# rcl_mini_v0_1.net
KiCad netlist of a schematic drawn in EAGLE
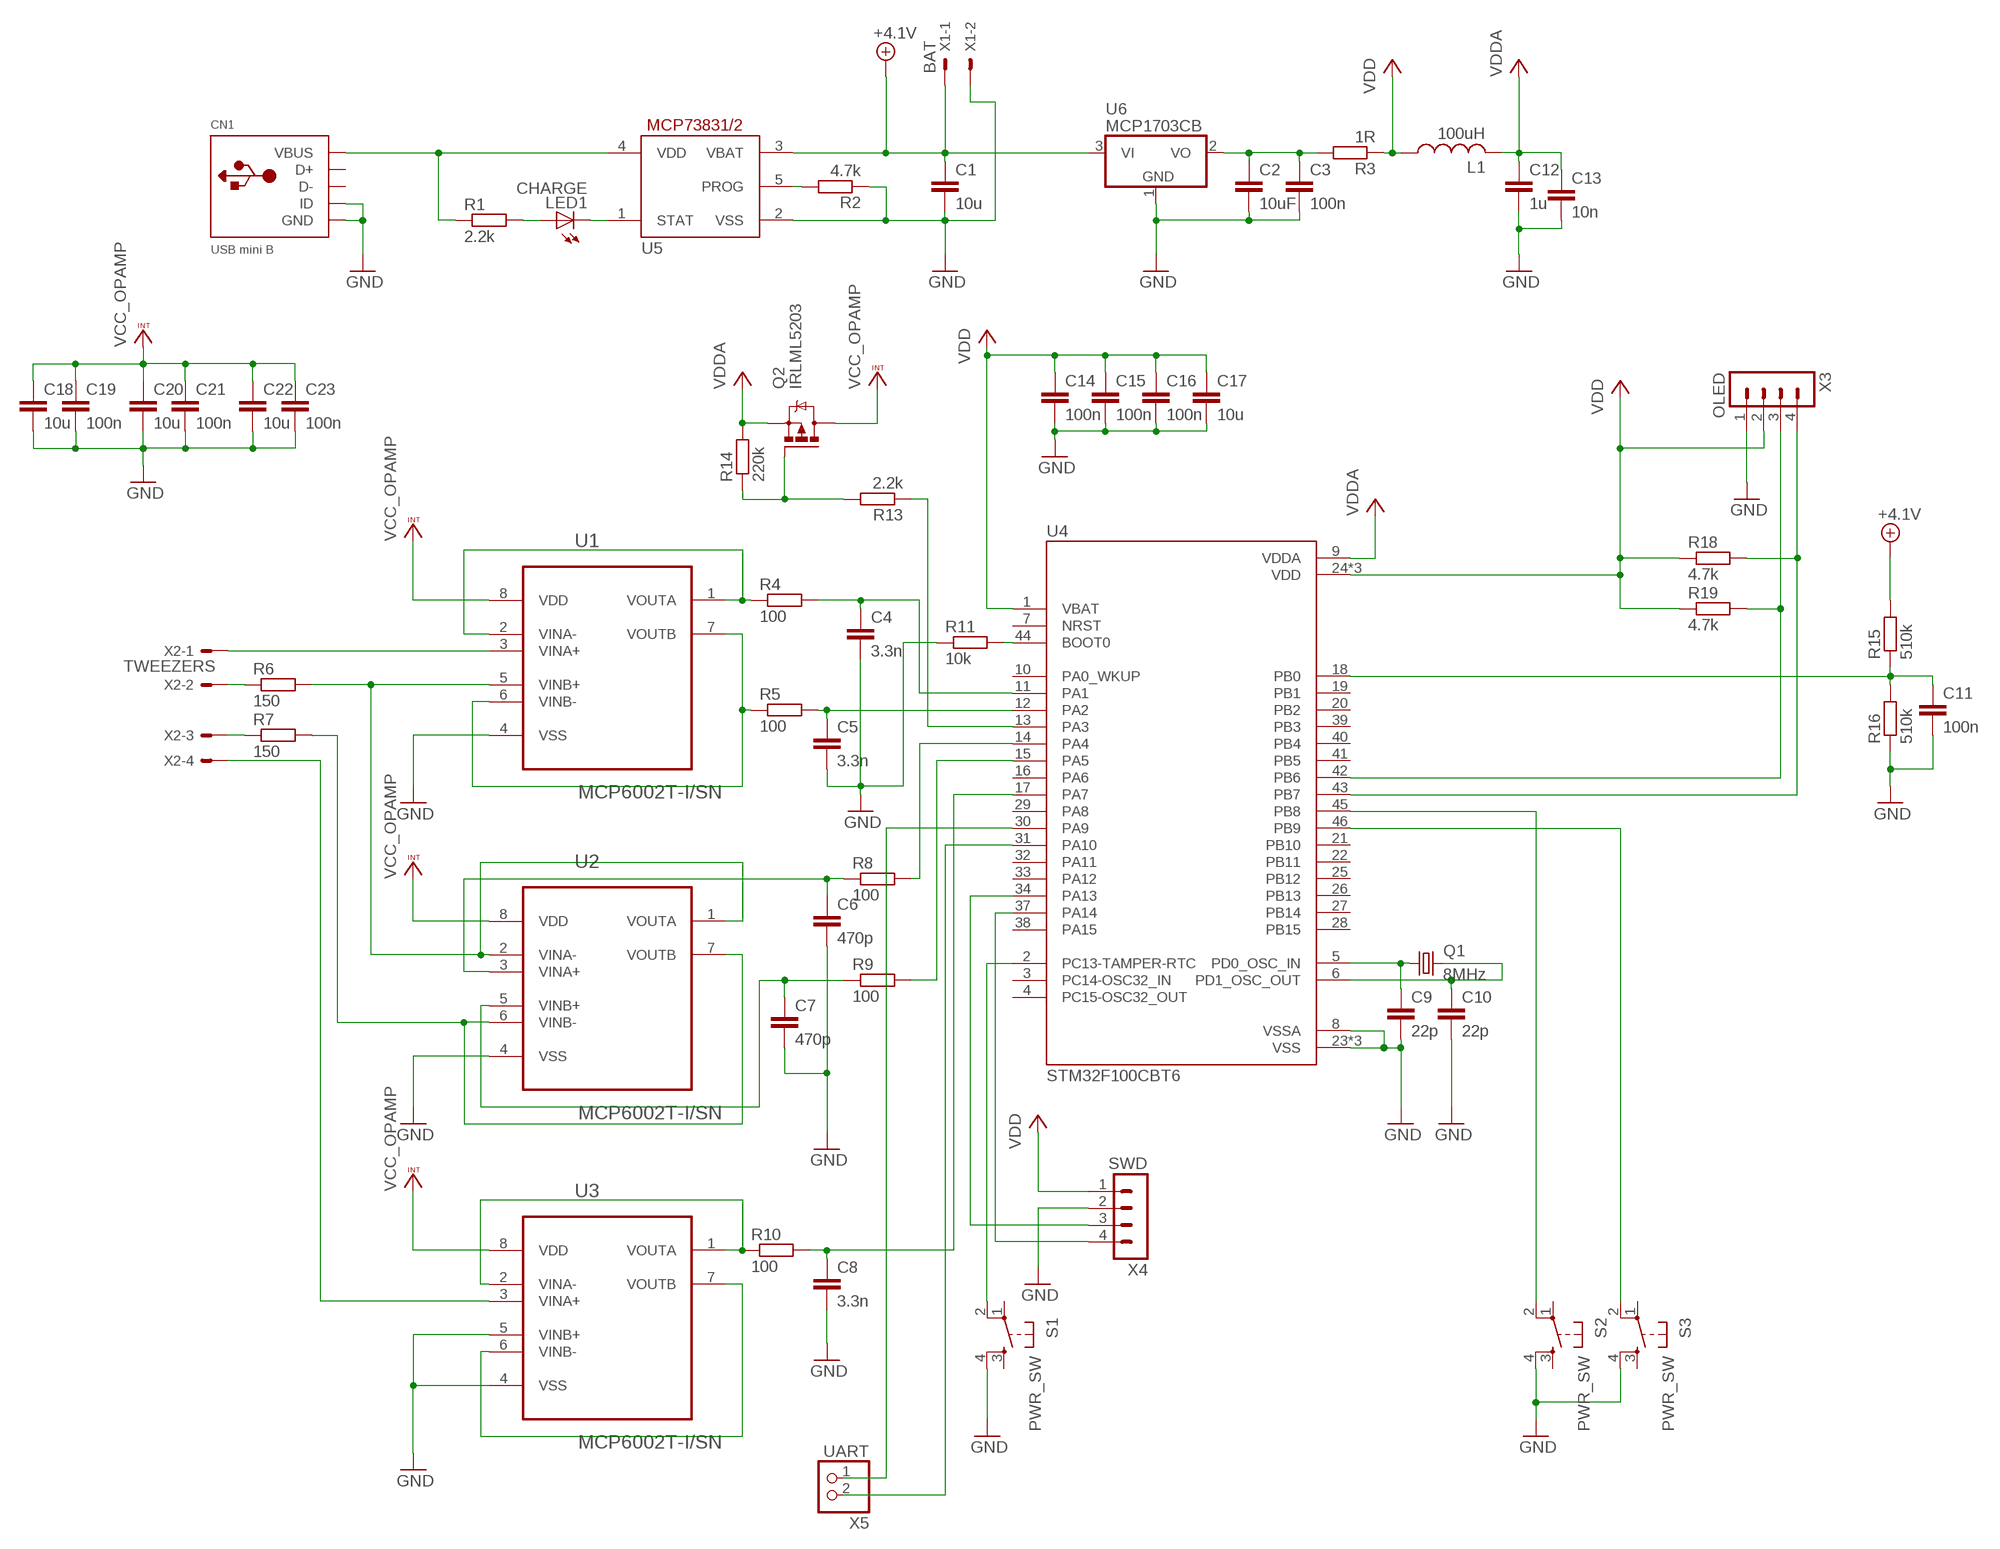
[diagram p0: schematic, sheet 1]

(export (version "E")
  (design (tool "Eeschema 10.0.6"))
  (components
    (comp (ref "C1")
      (value "10u")
      (footprint "eagle-import:C0805")
      (libsource (lib "eagle-import") (part "C-EUC0805"))
    )
    (comp (ref "C2")
      (value "10uF")
      (footprint "eagle-import:C0805")
      (libsource (lib "eagle-import") (part "C-EUC0805"))
    )
    (comp (ref "C3")
      (value "100n")
      (footprint "eagle-import:C0805")
      (libsource (lib "eagle-import") (part "C-EUC0805"))
    )
    (comp (ref "C4")
      (value "3.3n")
      (footprint "eagle-import:C0805")
      (libsource (lib "eagle-import") (part "C-EUC0805"))
    )
    (comp (ref "C5")
      (value "3.3n")
      (footprint "eagle-import:C0805")
      (libsource (lib "eagle-import") (part "C-EUC0805"))
    )
    (comp (ref "C6")
      (value "470p")
      (footprint "eagle-import:C0805")
      (libsource (lib "eagle-import") (part "C-EUC0805"))
    )
    (comp (ref "C7")
      (value "470p")
      (footprint "eagle-import:C0805")
      (libsource (lib "eagle-import") (part "C-EUC0805"))
    )
    (comp (ref "C8")
      (value "3.3n")
      (footprint "eagle-import:C0805")
      (libsource (lib "eagle-import") (part "C-EUC0805"))
    )
    (comp (ref "C9")
      (value "22p")
      (footprint "eagle-import:C0805")
      (libsource (lib "eagle-import") (part "C-EUC0805"))
    )
    (comp (ref "C10")
      (value "22p")
      (footprint "eagle-import:C0805")
      (libsource (lib "eagle-import") (part "C-EUC0805"))
    )
    (comp (ref "C11")
      (value "100n")
      (footprint "eagle-import:C0805")
      (libsource (lib "eagle-import") (part "C-EUC0805"))
    )
    (comp (ref "C12")
      (value "1u")
      (footprint "eagle-import:C0805")
      (libsource (lib "eagle-import") (part "C-EUC0805"))
    )
    (comp (ref "C13")
      (value "10n")
      (footprint "eagle-import:C0805")
      (libsource (lib "eagle-import") (part "C-EUC0805"))
    )
    (comp (ref "C14")
      (value "100n")
      (footprint "eagle-import:C0805")
      (libsource (lib "eagle-import") (part "C-EUC0805"))
    )
    (comp (ref "C15")
      (value "100n")
      (footprint "eagle-import:C0805")
      (libsource (lib "eagle-import") (part "C-EUC0805"))
    )
    (comp (ref "C16")
      (value "100n")
      (footprint "eagle-import:C0805")
      (libsource (lib "eagle-import") (part "C-EUC0805"))
    )
    (comp (ref "C17")
      (value "10u")
      (footprint "eagle-import:C0805")
      (libsource (lib "eagle-import") (part "C-EUC0805"))
    )
    (comp (ref "C18")
      (value "10u")
      (footprint "eagle-import:C0805")
      (libsource (lib "eagle-import") (part "C-EUC0805"))
    )
    (comp (ref "C19")
      (value "100n")
      (footprint "eagle-import:C0805")
      (libsource (lib "eagle-import") (part "C-EUC0805"))
    )
    (comp (ref "C20")
      (value "10u")
      (footprint "eagle-import:C0805")
      (libsource (lib "eagle-import") (part "C-EUC0805"))
    )
    (comp (ref "C21")
      (value "100n")
      (footprint "eagle-import:C0805")
      (libsource (lib "eagle-import") (part "C-EUC0805"))
    )
    (comp (ref "C22")
      (value "10u")
      (footprint "eagle-import:C0805")
      (libsource (lib "eagle-import") (part "C-EUC0805"))
    )
    (comp (ref "C23")
      (value "100n")
      (footprint "eagle-import:C0805")
      (libsource (lib "eagle-import") (part "C-EUC0805"))
    )
    (comp (ref "CN1")
      (value "USB mini B")
      (footprint "eagle-import:USB-MINIB")
      (libsource (lib "eagle-import") (part "USBMINIB"))
    )
    (comp (ref "L1")
      (value "100uH")
      (footprint "eagle-import:L3216C")
      (libsource (lib "eagle-import") (part "L-USL3216C"))
    )
    (comp (ref "LED1")
      (value "CHARGE")
      (footprint "eagle-import:CHIPLED_1206")
      (libsource (lib "eagle-import") (part "LEDCHIPLED_1206"))
    )
    (comp (ref "Q1")
      (value "8MHz")
      (footprint "eagle-import:HC49UP")
      (libsource (lib "eagle-import") (part "CRYSTALHC49UP"))
    )
    (comp (ref "Q2")
      (value "IRLML5203")
      (footprint "eagle-import:MICRO3")
      (libsource (lib "eagle-import") (part "IRLML5203"))
    )
    (comp (ref "R1")
      (value "2.2k")
      (footprint "eagle-import:M0805")
      (libsource (lib "eagle-import") (part "R-EU_M0805"))
    )
    (comp (ref "R2")
      (value "4.7k")
      (footprint "eagle-import:M0805")
      (libsource (lib "eagle-import") (part "R-EU_M0805"))
    )
    (comp (ref "R3")
      (value "1R")
      (footprint "eagle-import:M0805")
      (libsource (lib "eagle-import") (part "R-EU_M0805"))
    )
    (comp (ref "R4")
      (value "100")
      (footprint "eagle-import:M0805")
      (libsource (lib "eagle-import") (part "R-EU_M0805"))
    )
    (comp (ref "R5")
      (value "100")
      (footprint "eagle-import:M0805")
      (libsource (lib "eagle-import") (part "R-EU_M0805"))
    )
    (comp (ref "R6")
      (value "150")
      (footprint "eagle-import:M0805")
      (libsource (lib "eagle-import") (part "R-EU_M0805"))
    )
    (comp (ref "R7")
      (value "150")
      (footprint "eagle-import:M0805")
      (libsource (lib "eagle-import") (part "R-EU_M0805"))
    )
    (comp (ref "R8")
      (value "100")
      (footprint "eagle-import:M0805")
      (libsource (lib "eagle-import") (part "R-EU_M0805"))
    )
    (comp (ref "R9")
      (value "100")
      (footprint "eagle-import:M0805")
      (libsource (lib "eagle-import") (part "R-EU_M0805"))
    )
    (comp (ref "R10")
      (value "100")
      (footprint "eagle-import:M0805")
      (libsource (lib "eagle-import") (part "R-EU_M0805"))
    )
    (comp (ref "R11")
      (value "10k")
      (footprint "eagle-import:M0805")
      (libsource (lib "eagle-import") (part "R-EU_M0805"))
    )
    (comp (ref "R13")
      (value "2.2k")
      (footprint "eagle-import:M0805")
      (libsource (lib "eagle-import") (part "R-EU_M0805"))
    )
    (comp (ref "R14")
      (value "220k")
      (footprint "eagle-import:M0805")
      (libsource (lib "eagle-import") (part "R-EU_M0805"))
    )
    (comp (ref "R15")
      (value "510k")
      (footprint "eagle-import:M0805")
      (libsource (lib "eagle-import") (part "R-EU_M0805"))
    )
    (comp (ref "R16")
      (value "510k")
      (footprint "eagle-import:M0805")
      (libsource (lib "eagle-import") (part "R-EU_M0805"))
    )
    (comp (ref "R18")
      (value "4.7k")
      (footprint "eagle-import:M0805")
      (libsource (lib "eagle-import") (part "R-EU_M0805"))
    )
    (comp (ref "R19")
      (value "4.7k")
      (footprint "eagle-import:M0805")
      (libsource (lib "eagle-import") (part "R-EU_M0805"))
    )
    (comp (ref "S1")
      (value "PWR_SW")
      (footprint "eagle-import:DTS-6")
      (libsource (lib "eagle-import") (part "DTS-6"))
    )
    (comp (ref "S2")
      (value "PWR_SW")
      (footprint "eagle-import:DTS-6")
      (libsource (lib "eagle-import") (part "DTS-6"))
    )
    (comp (ref "S3")
      (value "PWR_SW")
      (footprint "eagle-import:DTS-6")
      (libsource (lib "eagle-import") (part "DTS-6"))
    )
    (comp (ref "U1")
      (value "MCP6002T-I/SN")
      (footprint "eagle-import:SOP65P490X110-8N")
      (fields (field (name "MF") "Microchip") (field (name "MP") "MCP6002T-I/MS"))
      (libsource (lib "eagle-import") (part "MCP6002T-I/MS"))
    )
    (comp (ref "U2")
      (value "MCP6002T-I/SN")
      (footprint "eagle-import:SOP65P490X110-8N")
      (fields (field (name "MF") "Microchip") (field (name "MP") "MCP6002T-I/MS"))
      (libsource (lib "eagle-import") (part "MCP6002T-I/MS"))
    )
    (comp (ref "U3")
      (value "MCP6002T-I/SN")
      (footprint "eagle-import:SOP65P490X110-8N")
      (fields (field (name "MF") "Microchip") (field (name "MP") "MCP6002T-I/MS"))
      (libsource (lib "eagle-import") (part "MCP6002T-I/MS"))
    )
    (comp (ref "U4")
      (value "STM32F100CBT6")
      (footprint "eagle-import:QFP50P900X900X160-48N")
      (fields (field (name "MF") "STMicroelectronics") (field (name "MP") "STM32F103C8T6"))
      (libsource (lib "eagle-import") (part "STM32F103C8T6"))
    )
    (comp (ref "U5")
      (value "MCP73831/OT")
      (footprint "eagle-import:SOT23-5L")
      (libsource (lib "eagle-import") (part "MCP73831/OT"))
    )
    (comp (ref "U6")
      (value "MCP1703CB")
      (footprint "eagle-import:SOT23")
      (libsource (lib "eagle-import") (part "MCP1703CB"))
    )
    (comp (ref "UART")
      (value "X5")
      (footprint "eagle-import:1X02")
      (libsource (lib "eagle-import") (part "PINHD-1X2"))
    )
    (comp (ref "X1")
      (value "BAT")
      (footprint "eagle-import:22-23-2021")
      (fields (field (name "MF") "MOLEX") (field (name "MPN") "22-23-2021"))
      (libsource (lib "eagle-import") (part "22-23-2021"))
    )
    (comp (ref "X2")
      (value "TWEEZERS")
      (footprint "eagle-import:22-23-2041")
      (fields (field (name "MF") "MOLEX") (field (name "MPN") "22-23-2041"))
      (libsource (lib "eagle-import") (part "22-23-2041"))
    )
    (comp (ref "X3")
      (value "OLED")
      (footprint "eagle-import:MA04-1")
      (libsource (lib "eagle-import") (part "MA04-1"))
    )
    (comp (ref "X4")
      (value "SWD")
      (footprint "eagle-import:MA04-1")
      (libsource (lib "eagle-import") (part "MA04-1"))
    )
  )
  (nets
    (net (code "1") (name "+4.1V") (class "Default")
      (node (ref "C1") (pin "1") (pinfunction "1_1") (pintype "passive"))
      (node (ref "R15") (pin "2") (pinfunction "2_2") (pintype "passive"))
      (node (ref "U5") (pin "3") (pinfunction "VBAT_3") (pintype "bidirectional"))
      (node (ref "U6") (pin "3") (pinfunction "VI_3") (pintype "input"))
      (node (ref "X1") (pin "1") (pinfunction "S_1") (pintype "passive"))
    )
    (net (code "2") (name "GND") (class "Default")
      (node (ref "C1") (pin "2") (pinfunction "2_2") (pintype "passive"))
      (node (ref "C10") (pin "2") (pinfunction "2_2") (pintype "passive"))
      (node (ref "C11") (pin "2") (pinfunction "2_2") (pintype "passive"))
      (node (ref "C12") (pin "2") (pinfunction "2_2") (pintype "passive"))
      (node (ref "C13") (pin "2") (pinfunction "2_2") (pintype "passive"))
      (node (ref "C14") (pin "2") (pinfunction "2_2") (pintype "passive"))
      (node (ref "C15") (pin "2") (pinfunction "2_2") (pintype "passive"))
      (node (ref "C16") (pin "2") (pinfunction "2_2") (pintype "passive"))
      (node (ref "C17") (pin "2") (pinfunction "2_2") (pintype "passive"))
      (node (ref "C18") (pin "2") (pinfunction "2_2") (pintype "passive"))
      (node (ref "C19") (pin "2") (pinfunction "2_2") (pintype "passive"))
      (node (ref "C2") (pin "2") (pinfunction "2_2") (pintype "passive"))
      (node (ref "C20") (pin "2") (pinfunction "2_2") (pintype "passive"))
      (node (ref "C21") (pin "2") (pinfunction "2_2") (pintype "passive"))
      (node (ref "C22") (pin "2") (pinfunction "2_2") (pintype "passive"))
      (node (ref "C23") (pin "2") (pinfunction "2_2") (pintype "passive"))
      (node (ref "C3") (pin "2") (pinfunction "2_2") (pintype "passive"))
      (node (ref "C4") (pin "2") (pinfunction "2_2") (pintype "passive"))
      (node (ref "C5") (pin "2") (pinfunction "2_2") (pintype "passive"))
      (node (ref "C6") (pin "2") (pinfunction "2_2") (pintype "passive"))
      (node (ref "C7") (pin "2") (pinfunction "2_2") (pintype "passive"))
      (node (ref "C8") (pin "2") (pinfunction "2_2") (pintype "passive"))
      (node (ref "C9") (pin "2") (pinfunction "2_2") (pintype "passive"))
      (node (ref "CN1") (pin "GND") (pinfunction "GND_GND") (pintype "power_in"))
      (node (ref "CN1") (pin "ID") (pinfunction "ID_ID") (pintype "bidirectional"))
      (node (ref "R11") (pin "1") (pinfunction "1_1") (pintype "passive"))
      (node (ref "R16") (pin "1") (pinfunction "1_1") (pintype "passive"))
      (node (ref "R2") (pin "1") (pinfunction "1_1") (pintype "passive"))
      (node (ref "S1") (pin "4") (pinfunction "4_4") (pintype "passive"))
      (node (ref "S2") (pin "4") (pinfunction "4_4") (pintype "passive"))
      (node (ref "S3") (pin "4") (pinfunction "4_4") (pintype "passive"))
      (node (ref "U1") (pin "4") (pinfunction "VSS_4") (pintype "power_in"))
      (node (ref "U2") (pin "4") (pinfunction "VSS_4") (pintype "power_in"))
      (node (ref "U3") (pin "4") (pinfunction "VSS_4") (pintype "power_in"))
      (node (ref "U3") (pin "5") (pinfunction "VINB+_5") (pintype "input"))
      (node (ref "U4") (pin "23") (pinfunction "VSS_23") (pintype "power_in"))
      (node (ref "U4") (pin "35") (pinfunction "VSS_35") (pintype "power_in"))
      (node (ref "U4") (pin "47") (pinfunction "VSS_47") (pintype "power_in"))
      (node (ref "U4") (pin "8") (pinfunction "VSSA_8") (pintype "power_in"))
      (node (ref "U5") (pin "2") (pinfunction "VSS_2") (pintype "power_in"))
      (node (ref "U6") (pin "1") (pinfunction "GND_1") (pintype "passive"))
      (node (ref "X1") (pin "2") (pinfunction "S_2") (pintype "passive"))
      (node (ref "X3") (pin "1") (pinfunction "1_1") (pintype "passive"))
      (node (ref "X4") (pin "2") (pinfunction "2_2") (pintype "passive"))
    )
    (net (code "3") (name "Net-(LED1-PadA)") (class "Default")
      (node (ref "LED1") (pin "A") (pinfunction "A_A") (pintype "passive"))
      (node (ref "R1") (pin "2") (pinfunction "2_2") (pintype "passive"))
    )
    (net (code "4") (name "Net-(Q2-G)") (class "Default")
      (node (ref "Q2") (pin "1") (pinfunction "G_1") (pintype "passive"))
      (node (ref "R13") (pin "2") (pinfunction "2_2") (pintype "passive"))
      (node (ref "R14") (pin "1") (pinfunction "1_1") (pintype "passive"))
    )
    (net (code "5") (name "Net-(U1-VINA+)") (class "Default")
      (node (ref "U1") (pin "3") (pinfunction "VINA+_3") (pintype "input"))
      (node (ref "X2") (pin "1") (pinfunction "S_1") (pintype "passive"))
    )
    (net (code "6") (name "Net-(U1-VINA-)") (class "Default")
      (node (ref "R4") (pin "1") (pinfunction "1_1") (pintype "passive"))
      (node (ref "U1") (pin "1") (pinfunction "VOUTA_1") (pintype "output"))
      (node (ref "U1") (pin "2") (pinfunction "VINA-_2") (pintype "input"))
    )
    (net (code "7") (name "Net-(U1-VINB+)") (class "Default")
      (node (ref "R6") (pin "2") (pinfunction "2_2") (pintype "passive"))
      (node (ref "U1") (pin "5") (pinfunction "VINB+_5") (pintype "input"))
      (node (ref "U2") (pin "1") (pinfunction "VOUTA_1") (pintype "output"))
      (node (ref "U2") (pin "2") (pinfunction "VINA-_2") (pintype "input"))
    )
    (net (code "8") (name "Net-(U1-VINB-)") (class "Default")
      (node (ref "R5") (pin "1") (pinfunction "1_1") (pintype "passive"))
      (node (ref "U1") (pin "6") (pinfunction "VINB-_6") (pintype "input"))
      (node (ref "U1") (pin "7") (pinfunction "VOUTB_7") (pintype "output"))
    )
    (net (code "9") (name "Net-(U2-VINA+)") (class "Default")
      (node (ref "C6") (pin "1") (pinfunction "1_1") (pintype "passive"))
      (node (ref "R8") (pin "1") (pinfunction "1_1") (pintype "passive"))
      (node (ref "U2") (pin "3") (pinfunction "VINA+_3") (pintype "input"))
    )
    (net (code "10") (name "Net-(U2-VINB+)") (class "Default")
      (node (ref "C7") (pin "1") (pinfunction "1_1") (pintype "passive"))
      (node (ref "R9") (pin "1") (pinfunction "1_1") (pintype "passive"))
      (node (ref "U2") (pin "5") (pinfunction "VINB+_5") (pintype "input"))
    )
    (net (code "11") (name "Net-(U2-VINB-)") (class "Default")
      (node (ref "R7") (pin "2") (pinfunction "2_2") (pintype "passive"))
      (node (ref "U2") (pin "6") (pinfunction "VINB-_6") (pintype "input"))
      (node (ref "U2") (pin "7") (pinfunction "VOUTB_7") (pintype "output"))
    )
    (net (code "12") (name "Net-(U3-VINA+)") (class "Default")
      (node (ref "U3") (pin "3") (pinfunction "VINA+_3") (pintype "input"))
      (node (ref "X2") (pin "4") (pinfunction "S_4") (pintype "passive"))
    )
    (net (code "13") (name "Net-(U3-VINA-)") (class "Default")
      (node (ref "R10") (pin "1") (pinfunction "1_1") (pintype "passive"))
      (node (ref "U3") (pin "1") (pinfunction "VOUTA_1") (pintype "output"))
      (node (ref "U3") (pin "2") (pinfunction "VINA-_2") (pintype "input"))
    )
    (net (code "14") (name "Net-(U3-VINB-)") (class "Default")
      (node (ref "U3") (pin "6") (pinfunction "VINB-_6") (pintype "input"))
      (node (ref "U3") (pin "7") (pinfunction "VOUTB_7") (pintype "output"))
    )
    (net (code "15") (name "Net-(U4-BOOT0)") (class "Default")
      (node (ref "R11") (pin "2") (pinfunction "2_2") (pintype "passive"))
      (node (ref "U4") (pin "44") (pinfunction "BOOT0_44") (pintype "input"))
    )
    (net (code "16") (name "Net-(U4-PA1)") (class "Default")
      (node (ref "C4") (pin "1") (pinfunction "1_1") (pintype "passive"))
      (node (ref "R4") (pin "2") (pinfunction "2_2") (pintype "passive"))
      (node (ref "U4") (pin "11") (pinfunction "PA1_11") (pintype "bidirectional"))
    )
    (net (code "17") (name "Net-(U4-PA2)") (class "Default")
      (node (ref "C5") (pin "1") (pinfunction "1_1") (pintype "passive"))
      (node (ref "R5") (pin "2") (pinfunction "2_2") (pintype "passive"))
      (node (ref "U4") (pin "12") (pinfunction "PA2_12") (pintype "bidirectional"))
    )
    (net (code "18") (name "Net-(U4-PA3)") (class "Default")
      (node (ref "R13") (pin "1") (pinfunction "1_1") (pintype "passive"))
      (node (ref "U4") (pin "13") (pinfunction "PA3_13") (pintype "bidirectional"))
    )
    (net (code "19") (name "Net-(U4-PA4)") (class "Default")
      (node (ref "R8") (pin "2") (pinfunction "2_2") (pintype "passive"))
      (node (ref "U4") (pin "14") (pinfunction "PA4_14") (pintype "bidirectional"))
    )
    (net (code "20") (name "Net-(U4-PA5)") (class "Default")
      (node (ref "R9") (pin "2") (pinfunction "2_2") (pintype "passive"))
      (node (ref "U4") (pin "15") (pinfunction "PA5_15") (pintype "bidirectional"))
    )
    (net (code "21") (name "Net-(U4-PA7)") (class "Default")
      (node (ref "C8") (pin "1") (pinfunction "1_1") (pintype "passive"))
      (node (ref "R10") (pin "2") (pinfunction "2_2") (pintype "passive"))
      (node (ref "U4") (pin "17") (pinfunction "PA7_17") (pintype "bidirectional"))
    )
    (net (code "22") (name "Net-(U4-PA9)") (class "Default")
      (node (ref "U4") (pin "30") (pinfunction "PA9_30") (pintype "bidirectional"))
      (node (ref "UART") (pin "1") (pinfunction "1_1") (pintype "passive"))
    )
    (net (code "23") (name "Net-(U4-PA10)") (class "Default")
      (node (ref "U4") (pin "31") (pinfunction "PA10_31") (pintype "bidirectional"))
      (node (ref "UART") (pin "2") (pinfunction "2_2") (pintype "passive"))
    )
    (net (code "24") (name "Net-(U4-PA13)") (class "Default")
      (node (ref "U4") (pin "34") (pinfunction "PA13_34") (pintype "bidirectional"))
      (node (ref "X4") (pin "3") (pinfunction "3_3") (pintype "passive"))
    )
    (net (code "25") (name "Net-(U4-PA14)") (class "Default")
      (node (ref "U4") (pin "37") (pinfunction "PA14_37") (pintype "bidirectional"))
      (node (ref "X4") (pin "4") (pinfunction "4_4") (pintype "passive"))
    )
    (net (code "26") (name "Net-(U4-PB0)") (class "Default")
      (node (ref "C11") (pin "1") (pinfunction "1_1") (pintype "passive"))
      (node (ref "R15") (pin "1") (pinfunction "1_1") (pintype "passive"))
      (node (ref "R16") (pin "2") (pinfunction "2_2") (pintype "passive"))
      (node (ref "U4") (pin "18") (pinfunction "PB0_18") (pintype "bidirectional"))
    )
    (net (code "27") (name "Net-(U4-PB6)") (class "Default")
      (node (ref "R19") (pin "2") (pinfunction "2_2") (pintype "passive"))
      (node (ref "U4") (pin "42") (pinfunction "PB6_42") (pintype "bidirectional"))
      (node (ref "X3") (pin "3") (pinfunction "3_3") (pintype "passive"))
    )
    (net (code "28") (name "Net-(U4-PB7)") (class "Default")
      (node (ref "R18") (pin "2") (pinfunction "2_2") (pintype "passive"))
      (node (ref "U4") (pin "43") (pinfunction "PB7_43") (pintype "bidirectional"))
      (node (ref "X3") (pin "4") (pinfunction "4_4") (pintype "passive"))
    )
    (net (code "29") (name "Net-(U4-PB8)") (class "Default")
      (node (ref "S2") (pin "2") (pinfunction "2_2") (pintype "passive"))
      (node (ref "U4") (pin "45") (pinfunction "PB8_45") (pintype "bidirectional"))
    )
    (net (code "30") (name "Net-(U4-PB9)") (class "Default")
      (node (ref "S3") (pin "2") (pinfunction "2_2") (pintype "passive"))
      (node (ref "U4") (pin "46") (pinfunction "PB9_46") (pintype "bidirectional"))
    )
    (net (code "31") (name "Net-(U4-PC13-TAMPER-RTC)") (class "Default")
      (node (ref "S1") (pin "2") (pinfunction "2_2") (pintype "passive"))
      (node (ref "U4") (pin "2") (pinfunction "PC13-TAMPER-RTC_2") (pintype "bidirectional"))
    )
    (net (code "32") (name "Net-(U4-PD0_OSC_IN)") (class "Default")
      (node (ref "C9") (pin "1") (pinfunction "1_1") (pintype "passive"))
      (node (ref "Q1") (pin "1") (pinfunction "1_1") (pintype "passive"))
      (node (ref "U4") (pin "5") (pinfunction "PD0_OSC_IN_5") (pintype "bidirectional"))
    )
    (net (code "33") (name "Net-(U4-PD1_OSC_OUT)") (class "Default")
      (node (ref "C10") (pin "1") (pinfunction "1_1") (pintype "passive"))
      (node (ref "Q1") (pin "2") (pinfunction "2_2") (pintype "passive"))
      (node (ref "U4") (pin "6") (pinfunction "PD1_OSC_OUT_6") (pintype "bidirectional"))
    )
    (net (code "34") (name "Net-(U5-PROG)") (class "Default")
      (node (ref "R2") (pin "2") (pinfunction "2_2") (pintype "passive"))
      (node (ref "U5") (pin "5") (pinfunction "PROG_5") (pintype "input"))
    )
    (net (code "35") (name "Net-(U5-STAT)") (class "Default")
      (node (ref "LED1") (pin "C") (pinfunction "C_C") (pintype "passive"))
      (node (ref "U5") (pin "1") (pinfunction "STAT_1") (pintype "output"))
    )
    (net (code "36") (name "Net-(U5-VDD)") (class "Default")
      (node (ref "CN1") (pin "VBUS") (pinfunction "VBUS_VBUS") (pintype "power_in"))
      (node (ref "R1") (pin "1") (pinfunction "1_1") (pintype "passive"))
      (node (ref "U5") (pin "4") (pinfunction "VDD_4") (pintype "power_in"))
    )
    (net (code "37") (name "Net-(U6-VO)") (class "Default")
      (node (ref "C2") (pin "1") (pinfunction "1_1") (pintype "passive"))
      (node (ref "C3") (pin "1") (pinfunction "1_1") (pintype "passive"))
      (node (ref "R3") (pin "2") (pinfunction "2_2") (pintype "passive"))
      (node (ref "U6") (pin "2") (pinfunction "VO_2") (pintype "passive"))
    )
    (net (code "38") (name "Net-(X2B-S)") (class "Default")
      (node (ref "R6") (pin "1") (pinfunction "1_1") (pintype "passive"))
      (node (ref "X2") (pin "2") (pinfunction "S_2") (pintype "passive"))
    )
    (net (code "39") (name "Net-(X2C-S)") (class "Default")
      (node (ref "R7") (pin "1") (pinfunction "1_1") (pintype "passive"))
      (node (ref "X2") (pin "3") (pinfunction "S_3") (pintype "passive"))
    )
    (net (code "40") (name "VCC_OPAMP") (class "Default")
      (node (ref "C18") (pin "1") (pinfunction "1_1") (pintype "passive"))
      (node (ref "C19") (pin "1") (pinfunction "1_1") (pintype "passive"))
      (node (ref "C20") (pin "1") (pinfunction "1_1") (pintype "passive"))
      (node (ref "C21") (pin "1") (pinfunction "1_1") (pintype "passive"))
      (node (ref "C22") (pin "1") (pinfunction "1_1") (pintype "passive"))
      (node (ref "C23") (pin "1") (pinfunction "1_1") (pintype "passive"))
      (node (ref "Q2") (pin "3") (pinfunction "D_3") (pintype "passive"))
      (node (ref "U1") (pin "8") (pinfunction "VDD_8") (pintype "power_in"))
      (node (ref "U2") (pin "8") (pinfunction "VDD_8") (pintype "power_in"))
      (node (ref "U3") (pin "8") (pinfunction "VDD_8") (pintype "power_in"))
    )
    (net (code "41") (name "VDD") (class "Default")
      (node (ref "C14") (pin "1") (pinfunction "1_1") (pintype "passive"))
      (node (ref "C15") (pin "1") (pinfunction "1_1") (pintype "passive"))
      (node (ref "C16") (pin "1") (pinfunction "1_1") (pintype "passive"))
      (node (ref "C17") (pin "1") (pinfunction "1_1") (pintype "passive"))
      (node (ref "L1") (pin "1") (pinfunction "1_1") (pintype "passive"))
      (node (ref "R18") (pin "1") (pinfunction "1_1") (pintype "passive"))
      (node (ref "R19") (pin "1") (pinfunction "1_1") (pintype "passive"))
      (node (ref "R3") (pin "1") (pinfunction "1_1") (pintype "passive"))
      (node (ref "U4") (pin "1") (pinfunction "VBAT_1") (pintype "bidirectional"))
      (node (ref "U4") (pin "24") (pinfunction "VDD_24") (pintype "power_in"))
      (node (ref "U4") (pin "36") (pinfunction "VDD_36") (pintype "power_in"))
      (node (ref "U4") (pin "48") (pinfunction "VDD_48") (pintype "power_in"))
      (node (ref "X3") (pin "2") (pinfunction "2_2") (pintype "passive"))
      (node (ref "X4") (pin "1") (pinfunction "1_1") (pintype "passive"))
    )
    (net (code "42") (name "VDDA") (class "Default")
      (node (ref "C12") (pin "1") (pinfunction "1_1") (pintype "passive"))
      (node (ref "C13") (pin "1") (pinfunction "1_1") (pintype "passive"))
      (node (ref "L1") (pin "2") (pinfunction "2_2") (pintype "passive"))
      (node (ref "Q2") (pin "2") (pinfunction "S_2") (pintype "passive"))
      (node (ref "R14") (pin "2") (pinfunction "2_2") (pintype "passive"))
      (node (ref "U4") (pin "9") (pinfunction "VDDA_9") (pintype "power_in"))
    )
    (net (code "43") (name "unconnected-(CN1-PadD+)") (class "Default")
      (node (ref "CN1") (pin "D+") (pinfunction "D+_D+") (pintype "bidirectional"))
    )
    (net (code "44") (name "unconnected-(CN1-PadD-)") (class "Default")
      (node (ref "CN1") (pin "D-") (pinfunction "D-_D-") (pintype "bidirectional"))
    )
    (net (code "45") (name "unconnected-(S1-Pad1)") (class "Default")
      (node (ref "S1") (pin "1") (pinfunction "1_1") (pintype "passive"))
    )
    (net (code "46") (name "unconnected-(S1-Pad3)") (class "Default")
      (node (ref "S1") (pin "3") (pinfunction "3_3") (pintype "passive"))
    )
    (net (code "47") (name "unconnected-(S2-Pad1)") (class "Default")
      (node (ref "S2") (pin "1") (pinfunction "1_1") (pintype "passive"))
    )
    (net (code "48") (name "unconnected-(S2-Pad3)") (class "Default")
      (node (ref "S2") (pin "3") (pinfunction "3_3") (pintype "passive"))
    )
    (net (code "49") (name "unconnected-(S3-Pad1)") (class "Default")
      (node (ref "S3") (pin "1") (pinfunction "1_1") (pintype "passive"))
    )
    (net (code "50") (name "unconnected-(S3-Pad3)") (class "Default")
      (node (ref "S3") (pin "3") (pinfunction "3_3") (pintype "passive"))
    )
    (net (code "51") (name "unconnected-(U4-NRST-Pad7)") (class "Default")
      (node (ref "U4") (pin "7") (pinfunction "NRST_7") (pintype "input"))
    )
    (net (code "52") (name "unconnected-(U4-PA0_WKUP-Pad10)") (class "Default")
      (node (ref "U4") (pin "10") (pinfunction "PA0_WKUP_10") (pintype "bidirectional"))
    )
    (net (code "53") (name "unconnected-(U4-PA6-Pad16)") (class "Default")
      (node (ref "U4") (pin "16") (pinfunction "PA6_16") (pintype "bidirectional"))
    )
    (net (code "54") (name "unconnected-(U4-PA8-Pad29)") (class "Default")
      (node (ref "U4") (pin "29") (pinfunction "PA8_29") (pintype "bidirectional"))
    )
    (net (code "55") (name "unconnected-(U4-PA11-Pad32)") (class "Default")
      (node (ref "U4") (pin "32") (pinfunction "PA11_32") (pintype "bidirectional"))
    )
    (net (code "56") (name "unconnected-(U4-PA12-Pad33)") (class "Default")
      (node (ref "U4") (pin "33") (pinfunction "PA12_33") (pintype "bidirectional"))
    )
    (net (code "57") (name "unconnected-(U4-PA15-Pad38)") (class "Default")
      (node (ref "U4") (pin "38") (pinfunction "PA15_38") (pintype "bidirectional"))
    )
    (net (code "58") (name "unconnected-(U4-PB1-Pad19)") (class "Default")
      (node (ref "U4") (pin "19") (pinfunction "PB1_19") (pintype "bidirectional"))
    )
    (net (code "59") (name "unconnected-(U4-PB2-Pad20)") (class "Default")
      (node (ref "U4") (pin "20") (pinfunction "PB2_20") (pintype "bidirectional"))
    )
    (net (code "60") (name "unconnected-(U4-PB3-Pad39)") (class "Default")
      (node (ref "U4") (pin "39") (pinfunction "PB3_39") (pintype "bidirectional"))
    )
    (net (code "61") (name "unconnected-(U4-PB4-Pad40)") (class "Default")
      (node (ref "U4") (pin "40") (pinfunction "PB4_40") (pintype "bidirectional"))
    )
    (net (code "62") (name "unconnected-(U4-PB5-Pad41)") (class "Default")
      (node (ref "U4") (pin "41") (pinfunction "PB5_41") (pintype "bidirectional"))
    )
    (net (code "63") (name "unconnected-(U4-PB10-Pad21)") (class "Default")
      (node (ref "U4") (pin "21") (pinfunction "PB10_21") (pintype "bidirectional"))
    )
    (net (code "64") (name "unconnected-(U4-PB11-Pad22)") (class "Default")
      (node (ref "U4") (pin "22") (pinfunction "PB11_22") (pintype "bidirectional"))
    )
    (net (code "65") (name "unconnected-(U4-PB12-Pad25)") (class "Default")
      (node (ref "U4") (pin "25") (pinfunction "PB12_25") (pintype "bidirectional"))
    )
    (net (code "66") (name "unconnected-(U4-PB13-Pad26)") (class "Default")
      (node (ref "U4") (pin "26") (pinfunction "PB13_26") (pintype "bidirectional"))
    )
    (net (code "67") (name "unconnected-(U4-PB14-Pad27)") (class "Default")
      (node (ref "U4") (pin "27") (pinfunction "PB14_27") (pintype "bidirectional"))
    )
    (net (code "68") (name "unconnected-(U4-PB15-Pad28)") (class "Default")
      (node (ref "U4") (pin "28") (pinfunction "PB15_28") (pintype "bidirectional"))
    )
    (net (code "69") (name "unconnected-(U4-PC14-OSC32_IN-Pad3)") (class "Default")
      (node (ref "U4") (pin "3") (pinfunction "PC14-OSC32_IN_3") (pintype "bidirectional"))
    )
    (net (code "70") (name "unconnected-(U4-PC15-OSC32_OUT-Pad4)") (class "Default")
      (node (ref "U4") (pin "4") (pinfunction "PC15-OSC32_OUT_4") (pintype "bidirectional"))
    )
  )
)
